# Integrators_Sergeant.net
KiCad netlist of a schematic drawn in Altium Designer
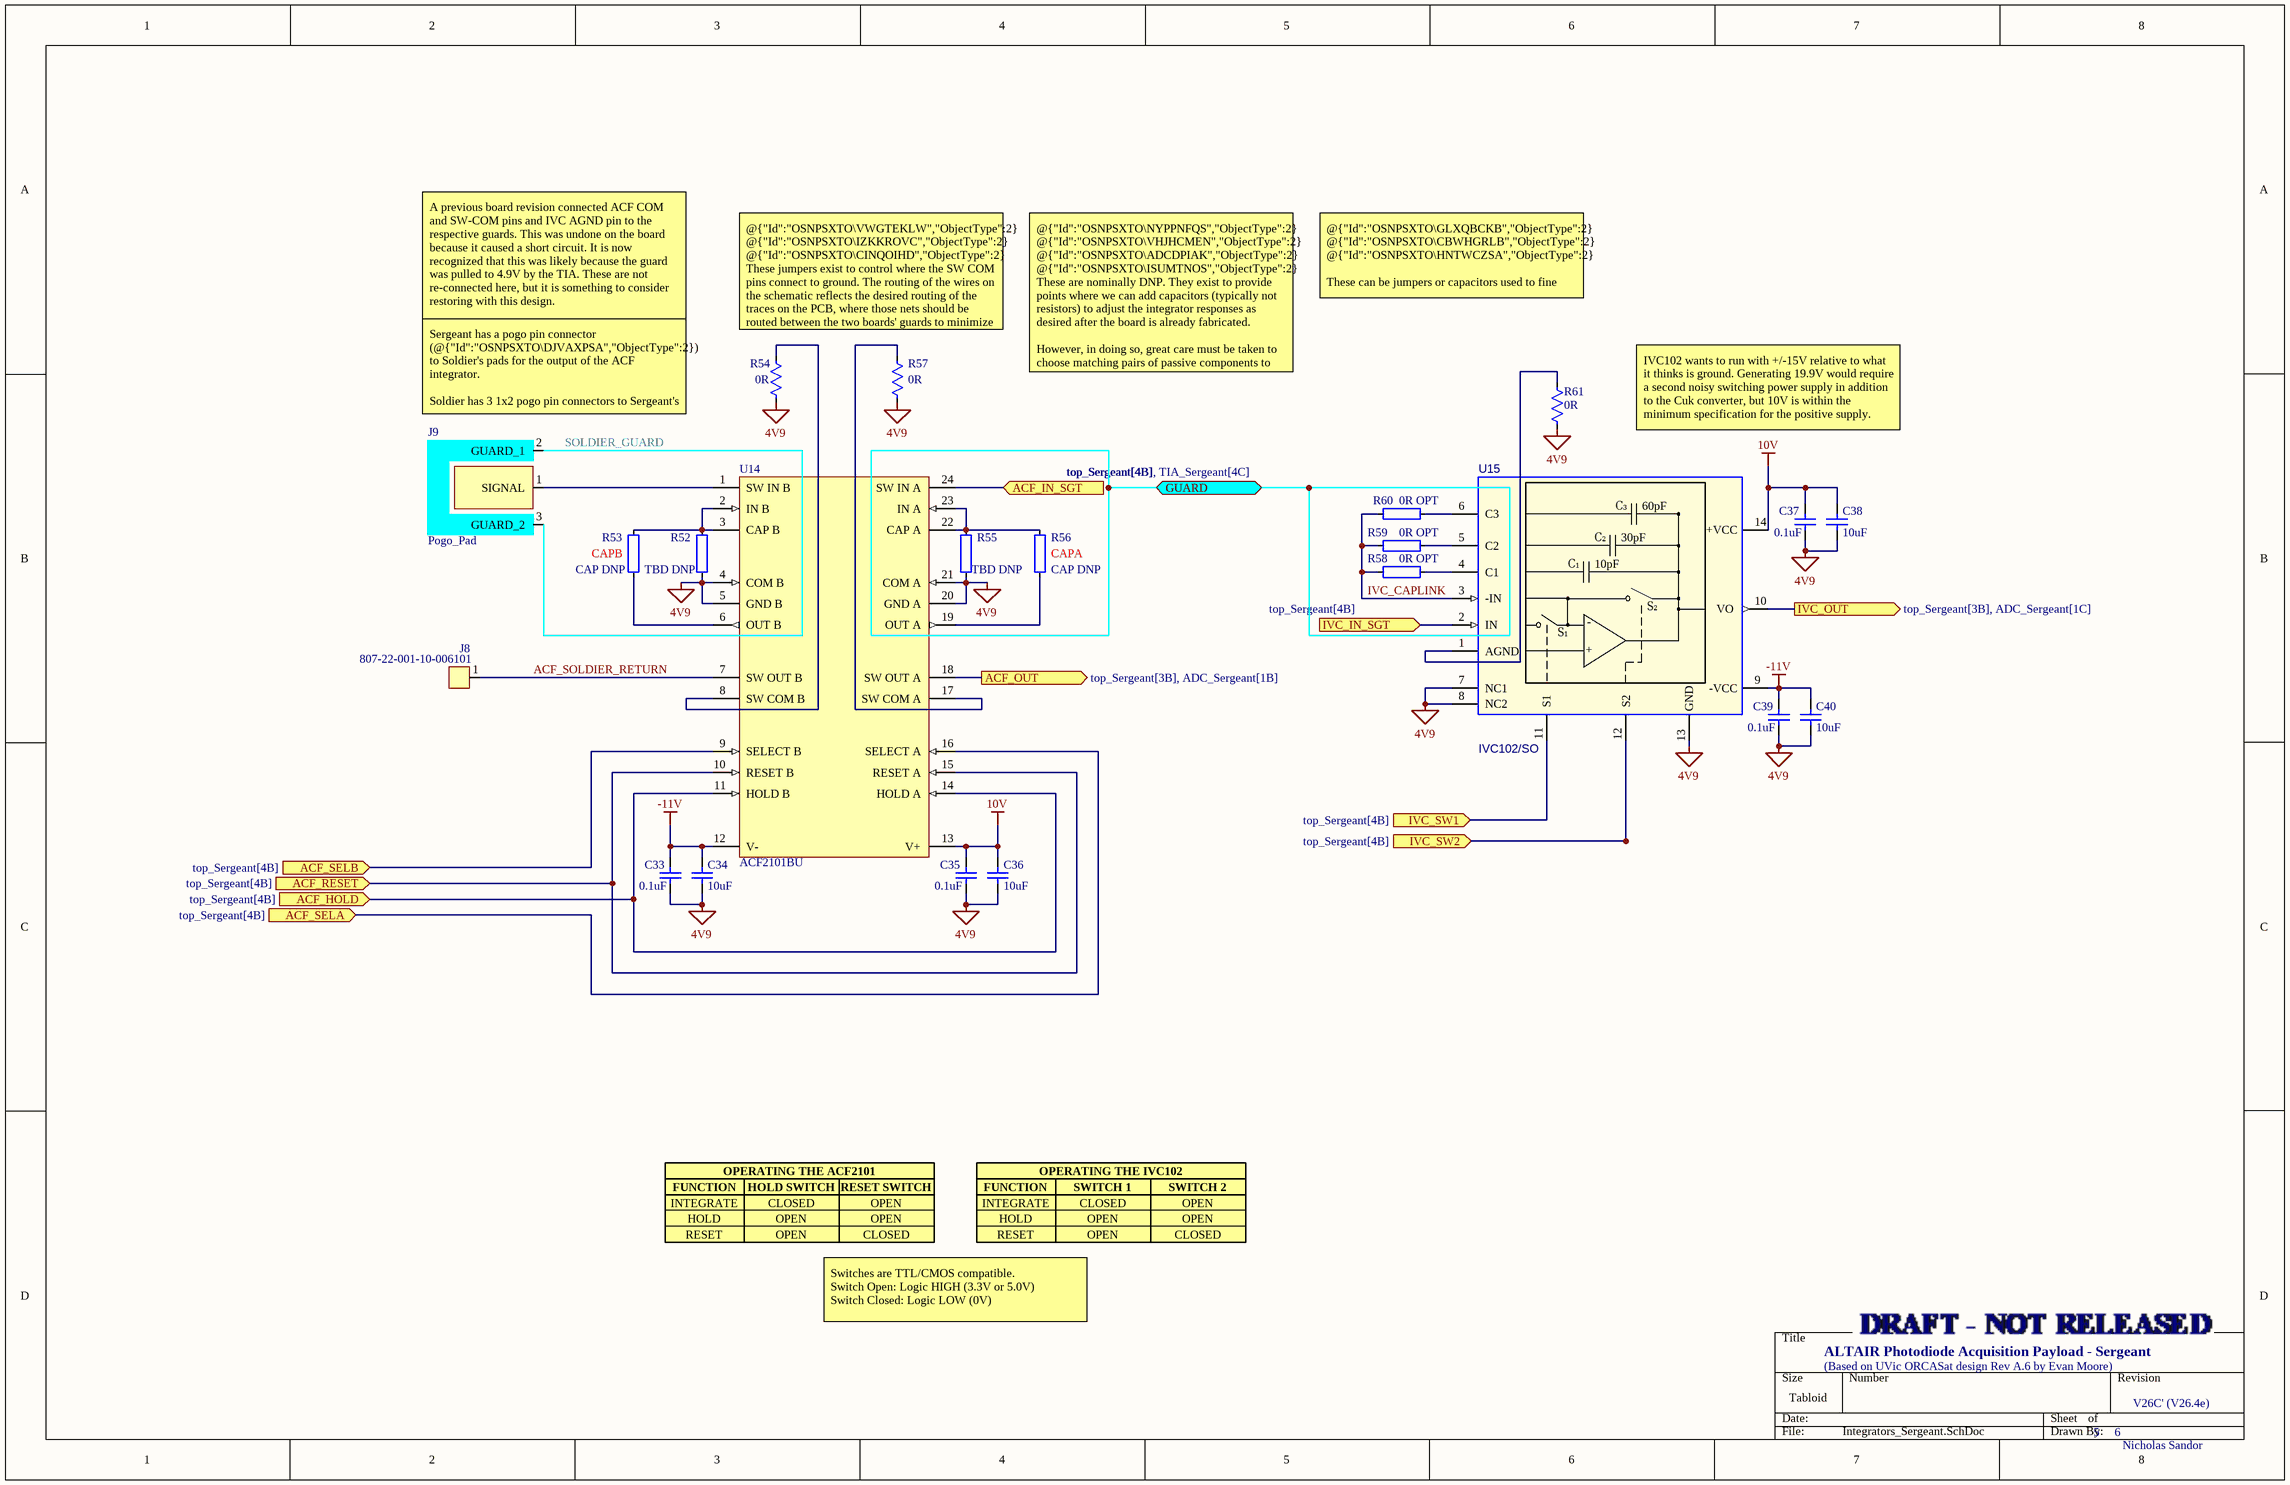
[diagram p0: Integrators_Sergeant.SchDoc]

(export (version "E")
  (design (tool "Eeschema 10.0.6"))
  (components
    (comp (ref "C33")
      (value "0.1uF")
      (footprint "CAP 0603 NON-IPC KEMET X7R")
      (description "Kemet C0603C104K5RACAUTO - Cap Ceramic 0.1uF 50V X7R 10% 0603 125C Paper T/R")
      (fields (field (name "MF") "Kemet") (field (name "MP") "C0603C104K5RACAUTO"))
      (libsource (lib "ALTAIR_PD_Capacitors") (part "CAP"))
    )
    (comp (ref "C34")
      (value "10uF")
      (footprint "CAP 0805 IPC MID DENSITY")
      (description "Murata GRM21BR61E106KA73L - Cap Ceramic 10uF 10% 25V X5R 0805")
      (fields (field (name "MF") "Murata") (field (name "MP") "GRM21BR61E106KA73L"))
      (libsource (lib "ALTAIR_PD_Capacitors") (part "CAP"))
    )
    (comp (ref "C35")
      (value "0.1uF")
      (footprint "CAP 0603 NON-IPC KEMET X7R")
      (description "Kemet C0603C104K5RACAUTO - Cap Ceramic 0.1uF 50V X7R 10% 0603 125C Paper T/R")
      (fields (field (name "MF") "Kemet") (field (name "MP") "C0603C104K5RACAUTO"))
      (libsource (lib "ALTAIR_PD_Capacitors") (part "CAP"))
    )
    (comp (ref "C36")
      (value "10uF")
      (footprint "CAP 0805 IPC MID DENSITY")
      (description "Murata GRM21BR61E106KA73L - Cap Ceramic 10uF 10% 25V X5R 0805")
      (fields (field (name "MF") "Murata") (field (name "MP") "GRM21BR61E106KA73L"))
      (libsource (lib "ALTAIR_PD_Capacitors") (part "CAP"))
    )
    (comp (ref "C37")
      (value "0.1uF")
      (footprint "CAP 0603 NON-IPC KEMET X7R")
      (description "Kemet C0603C104K5RACAUTO - Cap Ceramic 0.1uF 50V X7R 10% 0603 125C Paper T/R")
      (fields (field (name "MF") "Kemet") (field (name "MP") "C0603C104K5RACAUTO"))
      (libsource (lib "ALTAIR_PD_Capacitors") (part "CAP"))
    )
    (comp (ref "C38")
      (value "10uF")
      (footprint "CAP 0805 IPC MID DENSITY")
      (description "Murata GRM21BR61E106KA73L - Cap Ceramic 10uF 10% 25V X5R 0805")
      (fields (field (name "MF") "Murata") (field (name "MP") "GRM21BR61E106KA73L"))
      (libsource (lib "ALTAIR_PD_Capacitors") (part "CAP"))
    )
    (comp (ref "C39")
      (value "0.1uF")
      (footprint "CAP 0603 NON-IPC KEMET X7R")
      (description "Kemet C0603C104K5RACAUTO - Cap Ceramic 0.1uF 50V X7R 10% 0603 125C Paper T/R")
      (fields (field (name "MF") "Kemet") (field (name "MP") "C0603C104K5RACAUTO"))
      (libsource (lib "ALTAIR_PD_Capacitors") (part "CAP"))
    )
    (comp (ref "C40")
      (value "10uF")
      (footprint "CAP 0805 IPC MID DENSITY")
      (description "Murata GRM21BR61E106KA73L - Cap Ceramic 10uF 10% 25V X5R 0805")
      (fields (field (name "MF") "Murata") (field (name "MP") "GRM21BR61E106KA73L"))
      (libsource (lib "ALTAIR_PD_Capacitors") (part "CAP"))
    )
    (comp (ref "J8")
      (value "807-22-001-10-006101")
      (footprint "POGO PIN 807-22-001-10-006101")
      (description "Mill-Max Individual Insulated Pin 5.99mm Initial Height")
      (fields (field (name "MF") "Mill-Max"))
      (libsource (lib "ALTAIR_PD_Pogo") (part "807-22-001-10-006101"))
    )
    (comp (ref "J9")
      (value "Pogo_Pad")
      (footprint "POGO PAD SERGEANT")
      (description "Pad for Pogo Pins with Guard")
      (libsource (lib "ALTAIR_PD_Pogo") (part "Pogo_Pad"))
    )
    (comp (ref "R52")
      (value "TBD DNP")
      (footprint "RES 0402 IPC LOW DENSITY")
      (description "Yageo RC0402JR-070RL - Res 0 Ohms 1/16W SMD 0402")
      (fields (field (name "MF") "YAGEO") (field (name "MP") "RC0402JR-070RL"))
      (libsource (lib "ALTAIR_PD_Resistors") (part "IMPEDANCE"))
    )
    (comp (ref "R53")
      (value "CAP DNP")
      (footprint "RES 0402 IPC LOW DENSITY")
      (description "Yageo RC0402JR-070RL - Res 0 Ohms 1/16W SMD 0402")
      (fields (field (name "MF") "YAGEO") (field (name "MP") "RC0402JR-070RL"))
      (libsource (lib "ALTAIR_PD_Resistors") (part "IMPEDANCE"))
    )
    (comp (ref "R54")
      (value "0R")
      (footprint "RES 0402 IPC MID DENSITY")
      (description "Yageo RC0402JR-070RL - Res 0 Ohms 1/16W SMD 0402")
      (fields (field (name "MF") "YAGEO") (field (name "MP") "RC0402JR-070RL"))
      (libsource (lib "ALTAIR_PD_Resistors") (part "RES"))
    )
    (comp (ref "R55")
      (value "TBD DNP")
      (footprint "RES 0402 IPC LOW DENSITY")
      (description "Yageo RC0402JR-070RL - Res 0 Ohms 1/16W SMD 0402")
      (fields (field (name "MF") "YAGEO") (field (name "MP") "RC0402JR-070RL"))
      (libsource (lib "ALTAIR_PD_Resistors") (part "IMPEDANCE"))
    )
    (comp (ref "R56")
      (value "CAP DNP")
      (footprint "RES 0402 IPC LOW DENSITY")
      (description "Yageo RC0402JR-070RL - Res 0 Ohms 1/16W SMD 0402")
      (fields (field (name "MF") "YAGEO") (field (name "MP") "RC0402JR-070RL"))
      (libsource (lib "ALTAIR_PD_Resistors") (part "IMPEDANCE"))
    )
    (comp (ref "R57")
      (value "0R")
      (footprint "RES 0402 IPC MID DENSITY")
      (description "Yageo RC0402JR-070RL - Res 0 Ohms 1/16W SMD 0402")
      (fields (field (name "MF") "YAGEO") (field (name "MP") "RC0402JR-070RL"))
      (libsource (lib "ALTAIR_PD_Resistors") (part "RES"))
    )
    (comp (ref "R58")
      (value "0R OPT")
      (footprint "RES 0402 IPC LOW DENSITY")
      (description "Yageo RC0402JR-070RL - Res 0 Ohms 1/16W SMD 0402")
      (fields (field (name "MF") "YAGEO") (field (name "MP") "RC0402JR-070RL"))
      (libsource (lib "ALTAIR_PD_Resistors") (part "IMPEDANCE"))
    )
    (comp (ref "R59")
      (value "0R OPT")
      (footprint "RES 0402 IPC LOW DENSITY")
      (description "Yageo RC0402JR-070RL - Res 0 Ohms 1/16W SMD 0402")
      (fields (field (name "MF") "YAGEO") (field (name "MP") "RC0402JR-070RL"))
      (libsource (lib "ALTAIR_PD_Resistors") (part "IMPEDANCE"))
    )
    (comp (ref "R60")
      (value "0R OPT")
      (footprint "RES 0402 IPC LOW DENSITY")
      (description "Yageo RC0402JR-070RL - Res 0 Ohms 1/16W SMD 0402")
      (fields (field (name "MF") "YAGEO") (field (name "MP") "RC0402JR-070RL"))
      (libsource (lib "ALTAIR_PD_Resistors") (part "IMPEDANCE"))
    )
    (comp (ref "R61")
      (value "0R")
      (footprint "RES 0402 IPC MID DENSITY")
      (description "Yageo RC0402JR-070RL - Res 0 Ohms 1/16W SMD 0402")
      (fields (field (name "MF") "YAGEO") (field (name "MP") "RC0402JR-070RL"))
      (libsource (lib "ALTAIR_PD_Resistors") (part "RES"))
    )
    (comp (ref "U14")
      (value "ACF2101BU")
      (footprint "ALTAIR_PD_SOIC:24-SOIC 7.6MM WIDE LOW DENSITY")
      (fields (field (name "MF") "Texas Instruments"))
      (libsource (lib "ALTAIR_PD_Amplifiers") (part "ACF2101BU"))
    )
    (comp (ref "U15")
      (value "IVC102/SO")
      (footprint "14-SOIC 4MM WIDE LOW DENSITY")
      (description "Precision Switched Integrator Transimpedance Amplifier")
      (fields (field (name "MF") "Texas Instruments") (field (name "MP") "IVC102U"))
      (libsource (lib "ALTAIR_PD_Amplifiers") (part "IVC102/SO_5"))
    )
  )
  (nets
    (net (code "1") (name "-11V") (class "Default")
      (node (ref "C33") (pin "2") (pinfunction "2_2") (pintype "passive"))
      (node (ref "C34") (pin "2") (pinfunction "2_2") (pintype "passive"))
      (node (ref "C39") (pin "2") (pinfunction "2_2") (pintype "passive"))
      (node (ref "C40") (pin "2") (pinfunction "2_2") (pintype "passive"))
      (node (ref "U14") (pin "12") (pinfunction "V-_12") (pintype "power_in"))
      (node (ref "U15") (pin "9") (pinfunction "-VCC_9") (pintype "power_in"))
    )
    (net (code "2") (name "/ACF_HOLD") (class "Default")
      (node (ref "U14") (pin "11") (pinfunction "HOLD_B_11") (pintype "input"))
      (node (ref "U14") (pin "14") (pinfunction "HOLD_A_14") (pintype "input"))
    )
    (net (code "3") (name "/ACF_IN_SGT") (class "Default")
      (node (ref "U14") (pin "24") (pinfunction "SW_IN_A_24") (pintype "passive"))
    )
    (net (code "4") (name "/ACF_OUT") (class "Default")
      (node (ref "U14") (pin "18") (pinfunction "SW_OUT_A_18") (pintype "passive"))
    )
    (net (code "5") (name "/ACF_RESET") (class "Default")
      (node (ref "U14") (pin "10") (pinfunction "RESET_B_10") (pintype "input"))
      (node (ref "U14") (pin "15") (pinfunction "RESET_A_15") (pintype "input"))
    )
    (net (code "6") (name "/ACF_SELA") (class "Default")
      (node (ref "U14") (pin "16") (pinfunction "SELECT_A_16") (pintype "input"))
    )
    (net (code "7") (name "/ACF_SELB") (class "Default")
      (node (ref "U14") (pin "9") (pinfunction "SELECT_B_9") (pintype "input"))
    )
    (net (code "8") (name "/ACF_SOLDIER_RETURN") (class "Default")
      (node (ref "J8") (pin "1") (pinfunction "1_1") (pintype "passive"))
      (node (ref "U14") (pin "7") (pinfunction "SW_OUT_B_7") (pintype "passive"))
    )
    (net (code "10") (name "/IVC_CAPLINK") (class "Default")
      (node (ref "R58") (pin "1") (pinfunction "1_1") (pintype "passive"))
      (node (ref "R59") (pin "1") (pinfunction "1_1") (pintype "passive"))
      (node (ref "R60") (pin "1") (pinfunction "1_1") (pintype "passive"))
      (node (ref "U15") (pin "3") (pinfunction "-IN_3") (pintype "input"))
    )
    (net (code "11") (name "/IVC_IN_SGT") (class "Default")
      (node (ref "U15") (pin "2") (pinfunction "IN_2") (pintype "input"))
    )
    (net (code "12") (name "/IVC_OUT") (class "Default")
      (node (ref "U15") (pin "10") (pinfunction "VO_10") (pintype "output"))
    )
    (net (code "13") (name "/IVC_SW1") (class "Default")
      (node (ref "U15") (pin "11") (pinfunction "S1_11") (pintype "passive"))
    )
    (net (code "14") (name "/IVC_SW2") (class "Default")
      (node (ref "U15") (pin "12") (pinfunction "S2_12") (pintype "passive"))
    )
    (net (code "15") (name "/SOLDIER_GUARD") (class "Default")
      (node (ref "J9") (pin "2") (pinfunction "GUARD_1_2") (pintype "passive"))
      (node (ref "J9") (pin "3") (pinfunction "GUARD_2_3") (pintype "passive"))
    )
    (net (code "16") (name "4V9") (class "Default")
      (node (ref "C33") (pin "1") (pinfunction "1_1") (pintype "passive"))
      (node (ref "C34") (pin "1") (pinfunction "1_1") (pintype "passive"))
      (node (ref "C35") (pin "1") (pinfunction "1_1") (pintype "passive"))
      (node (ref "C36") (pin "1") (pinfunction "1_1") (pintype "passive"))
      (node (ref "C37") (pin "1") (pinfunction "1_1") (pintype "passive"))
      (node (ref "C38") (pin "1") (pinfunction "1_1") (pintype "passive"))
      (node (ref "C39") (pin "1") (pinfunction "1_1") (pintype "passive"))
      (node (ref "C40") (pin "1") (pinfunction "1_1") (pintype "passive"))
      (node (ref "R52") (pin "1") (pinfunction "1_1") (pintype "passive"))
      (node (ref "R54") (pin "2") (pinfunction "2_2") (pintype "passive"))
      (node (ref "R55") (pin "1") (pinfunction "1_1") (pintype "passive"))
      (node (ref "R57") (pin "2") (pinfunction "2_2") (pintype "passive"))
      (node (ref "R61") (pin "2") (pinfunction "2_2") (pintype "passive"))
      (node (ref "U14") (pin "20") (pinfunction "GND_A_20") (pintype "power_in"))
      (node (ref "U14") (pin "21") (pinfunction "COM_A_21") (pintype "input"))
      (node (ref "U14") (pin "4") (pinfunction "COM_B_4") (pintype "input"))
      (node (ref "U14") (pin "5") (pinfunction "GND_B_5") (pintype "power_in"))
      (node (ref "U15") (pin "13") (pinfunction "GND_13") (pintype "power_in"))
      (node (ref "U15") (pin "7") (pinfunction "NC1_7") (pintype "passive"))
      (node (ref "U15") (pin "8") (pinfunction "NC2_8") (pintype "passive"))
    )
    (net (code "17") (name "10V") (class "Default")
      (node (ref "C35") (pin "2") (pinfunction "2_2") (pintype "passive"))
      (node (ref "C36") (pin "2") (pinfunction "2_2") (pintype "passive"))
      (node (ref "C37") (pin "2") (pinfunction "2_2") (pintype "passive"))
      (node (ref "C38") (pin "2") (pinfunction "2_2") (pintype "passive"))
      (node (ref "U14") (pin "13") (pinfunction "V+_13") (pintype "power_in"))
      (node (ref "U15") (pin "14") (pinfunction "+VCC_14") (pintype "power_in"))
    )
    (net (code "18") (name "Net-(J9-SIGNAL)") (class "Default")
      (node (ref "J9") (pin "1") (pinfunction "SIGNAL_1") (pintype "passive"))
      (node (ref "U14") (pin "1") (pinfunction "SW_IN_B_1") (pintype "passive"))
    )
    (net (code "19") (name "Net-(U14-CAP_A)") (class "Default")
      (node (ref "R55") (pin "2") (pinfunction "2_2") (pintype "passive"))
      (node (ref "R56") (pin "2") (pinfunction "2_2") (pintype "passive"))
      (node (ref "U14") (pin "22") (pinfunction "CAP_A_22") (pintype "passive"))
      (node (ref "U14") (pin "23") (pinfunction "IN_A_23") (pintype "input"))
    )
    (net (code "20") (name "Net-(U14-CAP_B)") (class "Default")
      (node (ref "R52") (pin "2") (pinfunction "2_2") (pintype "passive"))
      (node (ref "R53") (pin "2") (pinfunction "2_2") (pintype "passive"))
      (node (ref "U14") (pin "2") (pinfunction "IN_B_2") (pintype "input"))
      (node (ref "U14") (pin "3") (pinfunction "CAP_B_3") (pintype "passive"))
    )
    (net (code "21") (name "Net-(U14-OUT_A)") (class "Default")
      (node (ref "R56") (pin "1") (pinfunction "1_1") (pintype "passive"))
      (node (ref "U14") (pin "19") (pinfunction "OUT_A_19") (pintype "output"))
    )
    (net (code "22") (name "Net-(U14-OUT_B)") (class "Default")
      (node (ref "R53") (pin "1") (pinfunction "1_1") (pintype "passive"))
      (node (ref "U14") (pin "6") (pinfunction "OUT_B_6") (pintype "output"))
    )
    (net (code "23") (name "Net-(U14-SW_COM_A)") (class "Default")
      (node (ref "R57") (pin "1") (pinfunction "1_1") (pintype "passive"))
      (node (ref "U14") (pin "17") (pinfunction "SW_COM_A_17") (pintype "passive"))
    )
    (net (code "24") (name "Net-(U14-SW_COM_B)") (class "Default")
      (node (ref "R54") (pin "1") (pinfunction "1_1") (pintype "passive"))
      (node (ref "U14") (pin "8") (pinfunction "SW_COM_B_8") (pintype "passive"))
    )
    (net (code "25") (name "Net-(U15-AGND)") (class "Default")
      (node (ref "R61") (pin "1") (pinfunction "1_1") (pintype "passive"))
      (node (ref "U15") (pin "1") (pinfunction "AGND_1") (pintype "power_in"))
    )
    (net (code "26") (name "Net-(U15-C1)") (class "Default")
      (node (ref "R58") (pin "2") (pinfunction "2_2") (pintype "passive"))
      (node (ref "U15") (pin "4") (pinfunction "C1_4") (pintype "passive"))
    )
    (net (code "27") (name "Net-(U15-C2)") (class "Default")
      (node (ref "R59") (pin "2") (pinfunction "2_2") (pintype "passive"))
      (node (ref "U15") (pin "5") (pinfunction "C2_5") (pintype "passive"))
    )
    (net (code "28") (name "Net-(U15-C3)") (class "Default")
      (node (ref "R60") (pin "2") (pinfunction "2_2") (pintype "passive"))
      (node (ref "U15") (pin "6") (pinfunction "C3_6") (pintype "passive"))
    )
  )
)
